# object_counter.net
KiCad netlist of a schematic drawn in EAGLE
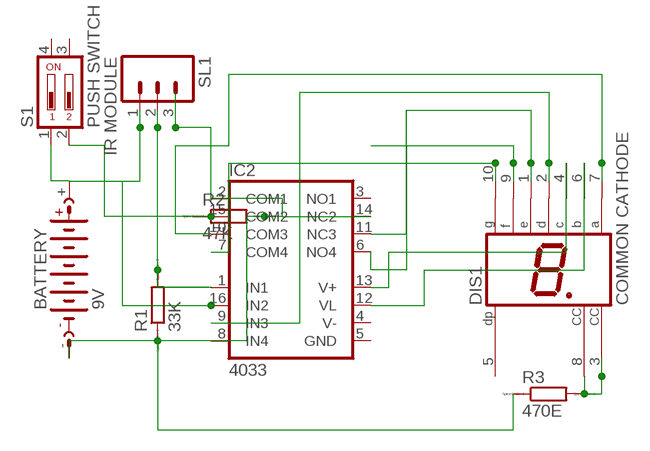
[diagram p0: schematic, sheet 1]

(export (version "E")
  (design (tool "Eeschema 10.0.6"))
  (components
    (comp (ref "BATTERY")
      (value "9V")
      (footprint "eagle-import:AB9V")
      (libsource (lib "eagle-import") (part "AB9V"))
    )
    (comp (ref "DIS1")
      (value "COMMON CATHODE")
      (footprint "eagle-import:HDSP-M")
      (libsource (lib "eagle-import") (part "HD-H103"))
    )
    (comp (ref "IC2")
      (value "4033")
      (footprint "eagle-import:DIL16")
      (fields (field (name "MPN") "MAX314EPE+"))
      (libsource (lib "eagle-import") (part "MAX314PEE"))
    )
    (comp (ref "R1")
      (value "33K")
      (footprint "eagle-import:0204_7")
      (libsource (lib "eagle-import") (part "R0204/7"))
    )
    (comp (ref "R2")
      (value "47K")
      (footprint "eagle-import:0204_7")
      (libsource (lib "eagle-import") (part "R0204/7"))
    )
    (comp (ref "R3")
      (value "470E")
      (footprint "eagle-import:0204_7")
      (libsource (lib "eagle-import") (part "R0204/7"))
    )
    (comp (ref "S1")
      (value "PUSH SWITCH")
      (footprint "eagle-import:DS-02")
      (libsource (lib "eagle-import") (part "DS02"))
    )
    (comp (ref "SL1")
      (value "IR MODULE")
      (footprint "eagle-import:03P")
      (libsource (lib "eagle-import") (part "M03"))
    )
  )
  (nets
    (net (code "1") (name "/GND") (class "Default")
      (node (ref "IC2") (pin "5") (pinfunction "GND_5") (pintype "power_in"))
    )
    (net (code "2") (name "/V-") (class "Default")
      (node (ref "IC2") (pin "4") (pinfunction "V-_4") (pintype "power_in"))
    )
    (net (code "3") (name "Net-(DIS1-A)") (class "Default")
      (node (ref "DIS1") (pin "7") (pinfunction "A_7") (pintype "passive"))
      (node (ref "IC2") (pin "10") (pinfunction "COM3_10") (pintype "passive"))
    )
    (net (code "4") (name "Net-(DIS1-B)") (class "Default")
      (node (ref "DIS1") (pin "6") (pinfunction "B_6") (pintype "passive"))
      (node (ref "IC2") (pin "12") (pinfunction "VL_12") (pintype "power_in"))
    )
    (net (code "5") (name "Net-(DIS1-C)") (class "Default")
      (node (ref "DIS1") (pin "4") (pinfunction "C_4") (pintype "passive"))
      (node (ref "IC2") (pin "13") (pinfunction "V+_13") (pintype "power_in"))
    )
    (net (code "6") (name "Net-(DIS1-CC-Pad3)") (class "Default")
      (node (ref "DIS1") (pin "3") (pinfunction "CC_3") (pintype "passive"))
      (node (ref "DIS1") (pin "8") (pinfunction "CC_8") (pintype "passive"))
      (node (ref "R3") (pin "2") (pinfunction "2_2") (pintype "passive"))
    )
    (net (code "7") (name "Net-(DIS1-D)") (class "Default")
      (node (ref "DIS1") (pin "2") (pinfunction "D_2") (pintype "passive"))
      (node (ref "IC2") (pin "9") (pinfunction "IN3_9") (pintype "input"))
    )
    (net (code "8") (name "Net-(DIS1-E)") (class "Default")
      (node (ref "DIS1") (pin "1") (pinfunction "E_1") (pintype "passive"))
      (node (ref "IC2") (pin "11") (pinfunction "NC3_11") (pintype "passive"))
    )
    (net (code "9") (name "Net-(DIS1-F)") (class "Default")
      (node (ref "DIS1") (pin "9") (pinfunction "F_9") (pintype "passive"))
      (node (ref "IC2") (pin "6") (pinfunction "NO4_6") (pintype "passive"))
    )
    (net (code "10") (name "Net-(DIS1-G)") (class "Default")
      (node (ref "DIS1") (pin "10") (pinfunction "G_10") (pintype "passive"))
      (node (ref "IC2") (pin "7") (pinfunction "COM4_7") (pintype "passive"))
    )
    (net (code "11") (name "Net-(IC2-COM1)") (class "Default")
      (node (ref "BATTERY") (pin "-") (pinfunction "-_-") (pintype "passive"))
      (node (ref "IC2") (pin "14") (pinfunction "NC2_14") (pintype "passive"))
      (node (ref "IC2") (pin "2") (pinfunction "COM1_2") (pintype "passive"))
      (node (ref "IC2") (pin "8") (pinfunction "IN4_8") (pintype "input"))
      (node (ref "R1") (pin "1") (pinfunction "1_1") (pintype "passive"))
      (node (ref "R2") (pin "2") (pinfunction "2_2") (pintype "passive"))
      (node (ref "R3") (pin "1") (pinfunction "1_1") (pintype "passive"))
      (node (ref "SL1") (pin "3") (pinfunction "3_3") (pintype "passive"))
    )
    (net (code "12") (name "Net-(IC2-COM2)") (class "Default")
      (node (ref "IC2") (pin "15") (pinfunction "COM2_15") (pintype "passive"))
      (node (ref "R2") (pin "1") (pinfunction "1_1") (pintype "passive"))
      (node (ref "S1") (pin "2") (pinfunction "2_2") (pintype "passive"))
    )
    (net (code "13") (name "Net-(IC2-IN1)") (class "Default")
      (node (ref "IC2") (pin "1") (pinfunction "IN1_1") (pintype "input"))
      (node (ref "R1") (pin "2") (pinfunction "2_2") (pintype "passive"))
      (node (ref "SL1") (pin "2") (pinfunction "2_2") (pintype "passive"))
    )
    (net (code "14") (name "Net-(IC2-IN2)") (class "Default")
      (node (ref "BATTERY") (pin "+") (pinfunction "+_+") (pintype "passive"))
      (node (ref "IC2") (pin "16") (pinfunction "IN2_16") (pintype "input"))
      (node (ref "S1") (pin "1") (pinfunction "1_1") (pintype "passive"))
      (node (ref "SL1") (pin "1") (pinfunction "1_1") (pintype "passive"))
    )
    (net (code "15") (name "unconnected-(DIS1-DP-Pad5)") (class "Default")
      (node (ref "DIS1") (pin "5") (pinfunction "DP_5") (pintype "passive"))
    )
    (net (code "16") (name "unconnected-(IC2-NO1-Pad3)") (class "Default")
      (node (ref "IC2") (pin "3") (pinfunction "NO1_3") (pintype "passive"))
    )
    (net (code "17") (name "unconnected-(S1-Pad3)") (class "Default")
      (node (ref "S1") (pin "3") (pinfunction "3_3") (pintype "passive"))
    )
    (net (code "18") (name "unconnected-(S1-Pad4)") (class "Default")
      (node (ref "S1") (pin "4") (pinfunction "4_4") (pintype "passive"))
    )
  )
)
